# mcu.net
KiCad netlist of a schematic drawn in Altium Designer
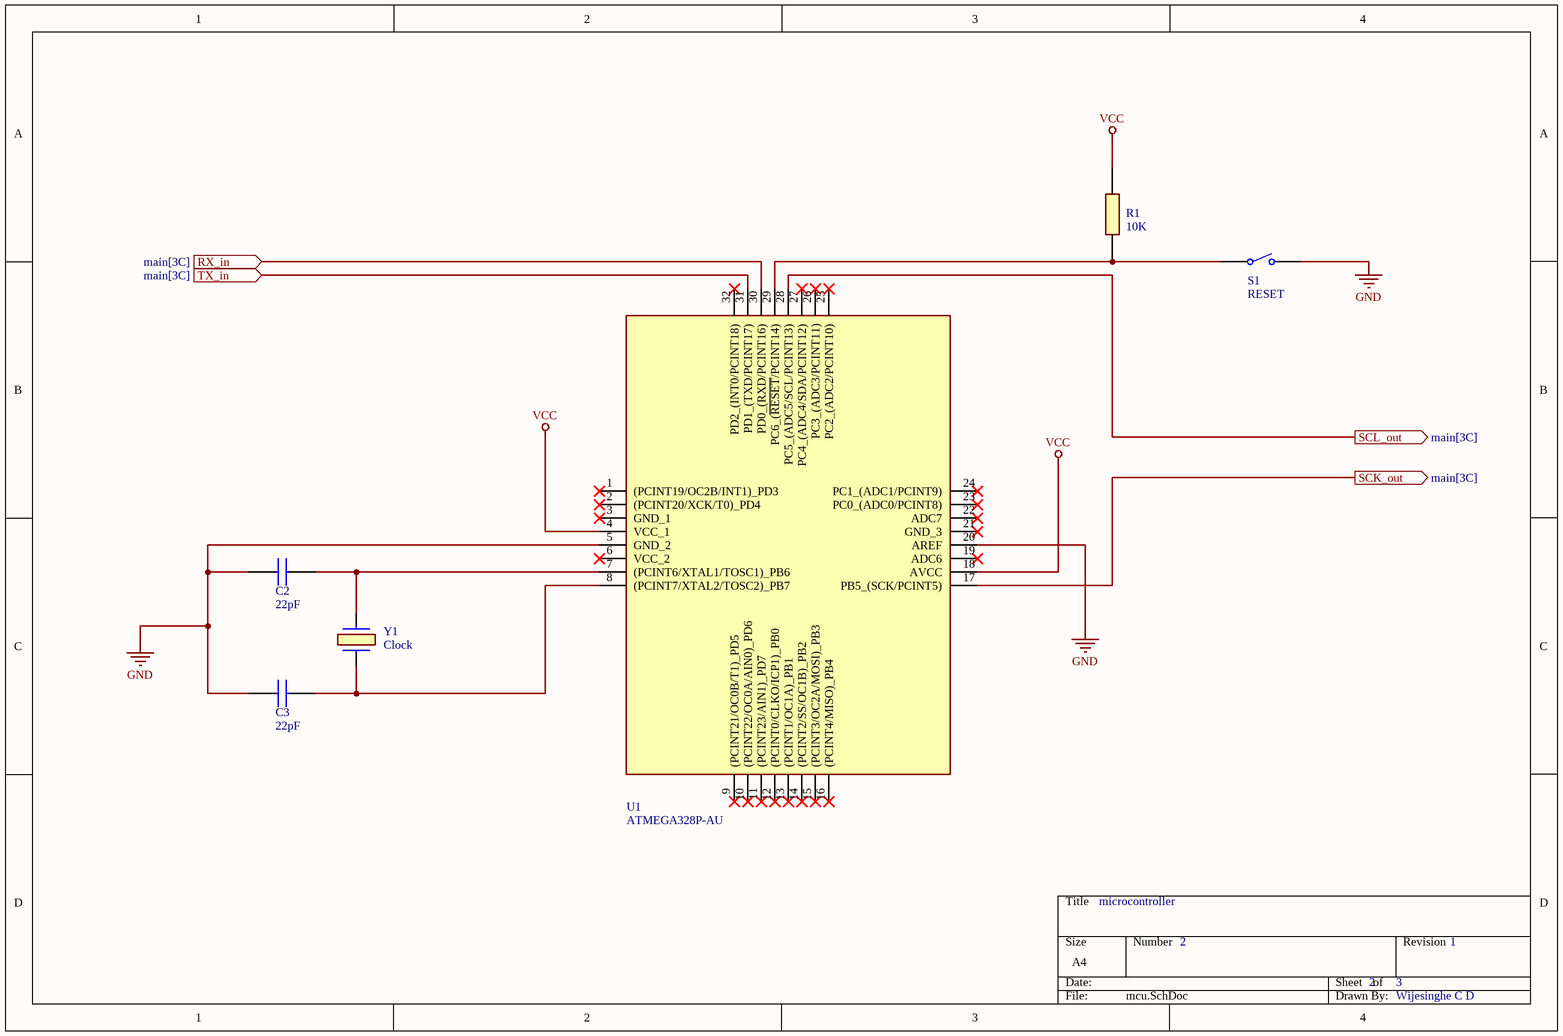
[diagram p0: mcu.SchDoc]

(export (version "E")
  (design (tool "Eeschema 10.0.6"))
  (components
    (comp (ref "C2")
      (value "22pF")
      (footprint "SamacSys:CAPC3216X100N")
      (description "Capacitor")
      (fields
        (field (name "MANUFACTURER_PART_NUMBER") "CL31C220JBCNNNC")
        (field (name "MOUSER PART NUMBER") "187-CL31C220JBCNNNC")
      )
      (libsource (lib "*") (part "CL31C220JBCNNNC"))
    )
    (comp (ref "C3")
      (value "22pF")
      (footprint "SamacSys:CAPC3216X100N")
      (description "Capacitor")
      (fields
        (field (name "MANUFACTURER_PART_NUMBER") "CL31C220JBCNNNC")
        (field (name "MOUSER PART NUMBER") "187-CL31C220JBCNNNC")
      )
      (libsource (lib "*") (part "CL31C220JBCNNNC"))
    )
    (comp (ref "R1")
      (value "10K")
      (footprint "SamacSys:RESC2012X75N")
      (description "Resistor")
      (fields
        (field (name "MANUFACTURER_PART_NUMBER") "ERJ-P6WF1002V")
        (field (name "MOUSER PART NUMBER") "667-ERJ-P6WF1002V")
      )
      (libsource (lib "*") (part "ERJ-P6WF1002V"))
    )
    (comp (ref "S1")
      (value "RESET")
      (footprint "TECO-FSMSM-2_V")
      (description "FSMSM Push Button Switch, 50 mA, -35 to 85 degC, 2-Pin SMD, RoHS, Bulk")
      (fields (field (name "MANUFACTURER") "TE Connectivity"))
      (libsource (lib "Altium Content Vault") (part "SW-SPST-2_C"))
    )
    (comp (ref "U1")
      (value "ATMEGA328P-AU")
      (footprint "SamacSys:QFP80P900X900X120-32N")
      (description "Integrated Circuit")
      (fields (field (name "MOUSER PART NUMBER") "556-ATMEGA328P-AU"))
      (libsource (lib "*") (part "ATMEGA328P-AU"))
    )
    (comp (ref "Y1")
      (value "Clock")
      (footprint "SamacSys:ECS160203XTR")
      (description "Crystal or Oscillator")
      (fields
        (field (name "MANUFACTURER_PART_NUMBER") "ECS-160-20-3X-TR")
        (field (name "MOUSER PART NUMBER") "520-160-20-3XT")
      )
      (libsource (lib "*") (part "ECS-160-20-3X-TR"))
    )
  )
  (nets
    (net (code "1") (name "/RX_in") (class "Default")
      (node (ref "U1") (pin "30") (pinfunction "PD0_(RXD/PCINT16)_30") (pintype "passive"))
    )
    (net (code "2") (name "/SCK_out") (class "Default")
      (node (ref "U1") (pin "17") (pinfunction "PB5_(SCK/PCINT5)_17") (pintype "passive"))
    )
    (net (code "3") (name "/SCL_out") (class "Default")
      (node (ref "U1") (pin "28") (pinfunction "PC5_(ADC5/SCL/PCINT13)_28") (pintype "passive"))
    )
    (net (code "4") (name "/TX_in") (class "Default")
      (node (ref "U1") (pin "31") (pinfunction "PD1_(TXD/PCINT17)_31") (pintype "passive"))
    )
    (net (code "5") (name "GND") (class "Default")
      (node (ref "C2") (pin "1") (pinfunction "1_1") (pintype "passive"))
      (node (ref "C3") (pin "1") (pinfunction "1_1") (pintype "passive"))
      (node (ref "S1") (pin "2") (pinfunction "2_2") (pintype "passive"))
      (node (ref "U1") (pin "20") (pinfunction "AREF_20") (pintype "passive"))
      (node (ref "U1") (pin "5") (pinfunction "GND_2_5") (pintype "passive"))
    )
    (net (code "6") (name "Net-(U1-(PCINT6{slash}XTAL1{slash}TOSC1)_PB6)") (class "Default")
      (node (ref "C2") (pin "2") (pinfunction "2_2") (pintype "passive"))
      (node (ref "U1") (pin "7") (pinfunction "(PCINT6/XTAL1/TOSC1)_PB6_7") (pintype "passive"))
      (node (ref "Y1") (pin "1") (pinfunction "X1_1") (pintype "passive"))
    )
    (net (code "7") (name "Net-(U1-(PCINT7{slash}XTAL2{slash}TOSC2)_PB7)") (class "Default")
      (node (ref "C3") (pin "2") (pinfunction "2_2") (pintype "passive"))
      (node (ref "U1") (pin "8") (pinfunction "(PCINT7/XTAL2/TOSC2)_PB7_8") (pintype "passive"))
      (node (ref "Y1") (pin "2") (pinfunction "X2_2") (pintype "passive"))
    )
    (net (code "8") (name "Net-(U1-PC6_(~{RESET}{slash}PCINT14))") (class "Default")
      (node (ref "R1") (pin "1") (pinfunction "1_1") (pintype "passive"))
      (node (ref "S1") (pin "1") (pinfunction "1_1") (pintype "passive"))
      (node (ref "U1") (pin "29") (pinfunction "PC6_(~{RESET}/PCINT14)_29") (pintype "passive"))
    )
    (net (code "9") (name "VCC") (class "Default")
      (node (ref "R1") (pin "2") (pinfunction "2_2") (pintype "passive"))
      (node (ref "U1") (pin "18") (pinfunction "AVCC_18") (pintype "passive"))
      (node (ref "U1") (pin "4") (pinfunction "VCC_1_4") (pintype "passive"))
    )
    (net (code "10") (name "unconnected-(U1-(PCINT0{slash}CLKO{slash}ICP1)_PB0-Pad12)") (class "Default")
      (node (ref "U1") (pin "12") (pinfunction "(PCINT0/CLKO/ICP1)_PB0_12") (pintype "passive+no_connect"))
    )
    (net (code "11") (name "unconnected-(U1-(PCINT1{slash}OC1A)_PB1-Pad13)") (class "Default")
      (node (ref "U1") (pin "13") (pinfunction "(PCINT1/OC1A)_PB1_13") (pintype "passive+no_connect"))
    )
    (net (code "12") (name "unconnected-(U1-(PCINT2{slash}SS{slash}OC1B)_PB2-Pad14)") (class "Default")
      (node (ref "U1") (pin "14") (pinfunction "(PCINT2/SS/OC1B)_PB2_14") (pintype "passive+no_connect"))
    )
    (net (code "13") (name "unconnected-(U1-(PCINT3{slash}OC2A{slash}MOSI)_PB3-Pad15)") (class "Default")
      (node (ref "U1") (pin "15") (pinfunction "(PCINT3/OC2A/MOSI)_PB3_15") (pintype "passive+no_connect"))
    )
    (net (code "14") (name "unconnected-(U1-(PCINT4{slash}MISO)_PB4-Pad16)") (class "Default")
      (node (ref "U1") (pin "16") (pinfunction "(PCINT4/MISO)_PB4_16") (pintype "passive+no_connect"))
    )
    (net (code "15") (name "unconnected-(U1-(PCINT19{slash}OC2B{slash}INT1)_PD3-Pad1)") (class "Default")
      (node (ref "U1") (pin "1") (pinfunction "(PCINT19/OC2B/INT1)_PD3_1") (pintype "passive+no_connect"))
    )
    (net (code "16") (name "unconnected-(U1-(PCINT20{slash}XCK{slash}T0)_PD4-Pad2)") (class "Default")
      (node (ref "U1") (pin "2") (pinfunction "(PCINT20/XCK/T0)_PD4_2") (pintype "passive+no_connect"))
    )
    (net (code "17") (name "unconnected-(U1-(PCINT21{slash}OC0B{slash}T1)_PD5-Pad9)") (class "Default")
      (node (ref "U1") (pin "9") (pinfunction "(PCINT21/OC0B/T1)_PD5_9") (pintype "passive+no_connect"))
    )
    (net (code "18") (name "unconnected-(U1-(PCINT22{slash}OC0A{slash}AIN0)_PD6-Pad10)") (class "Default")
      (node (ref "U1") (pin "10") (pinfunction "(PCINT22/OC0A/AIN0)_PD6_10") (pintype "passive+no_connect"))
    )
    (net (code "19") (name "unconnected-(U1-(PCINT23{slash}AIN1)_PD7-Pad11)") (class "Default")
      (node (ref "U1") (pin "11") (pinfunction "(PCINT23/AIN1)_PD7_11") (pintype "passive+no_connect"))
    )
    (net (code "20") (name "unconnected-(U1-ADC6-Pad19)") (class "Default")
      (node (ref "U1") (pin "19") (pinfunction "ADC6_19") (pintype "passive+no_connect"))
    )
    (net (code "21") (name "unconnected-(U1-ADC7-Pad22)") (class "Default")
      (node (ref "U1") (pin "22") (pinfunction "ADC7_22") (pintype "passive+no_connect"))
    )
    (net (code "22") (name "unconnected-(U1-GND_1-Pad3)") (class "Default")
      (node (ref "U1") (pin "3") (pinfunction "GND_1_3") (pintype "passive+no_connect"))
    )
    (net (code "23") (name "unconnected-(U1-GND_3-Pad21)") (class "Default")
      (node (ref "U1") (pin "21") (pinfunction "GND_3_21") (pintype "passive+no_connect"))
    )
    (net (code "24") (name "unconnected-(U1-PC0_(ADC0{slash}PCINT8)-Pad23)") (class "Default")
      (node (ref "U1") (pin "23") (pinfunction "PC0_(ADC0/PCINT8)_23") (pintype "passive+no_connect"))
    )
    (net (code "25") (name "unconnected-(U1-PC1_(ADC1{slash}PCINT9)-Pad24)") (class "Default")
      (node (ref "U1") (pin "24") (pinfunction "PC1_(ADC1/PCINT9)_24") (pintype "passive+no_connect"))
    )
    (net (code "26") (name "unconnected-(U1-PC2_(ADC2{slash}PCINT10)-Pad25)") (class "Default")
      (node (ref "U1") (pin "25") (pinfunction "PC2_(ADC2/PCINT10)_25") (pintype "passive+no_connect"))
    )
    (net (code "27") (name "unconnected-(U1-PC3_(ADC3{slash}PCINT11)-Pad26)") (class "Default")
      (node (ref "U1") (pin "26") (pinfunction "PC3_(ADC3/PCINT11)_26") (pintype "passive+no_connect"))
    )
    (net (code "28") (name "unconnected-(U1-PC4_(ADC4{slash}SDA{slash}PCINT12)-Pad27)") (class "Default")
      (node (ref "U1") (pin "27") (pinfunction "PC4_(ADC4/SDA/PCINT12)_27") (pintype "passive+no_connect"))
    )
    (net (code "29") (name "unconnected-(U1-PD2_(INT0{slash}PCINT18)-Pad32)") (class "Default")
      (node (ref "U1") (pin "32") (pinfunction "PD2_(INT0/PCINT18)_32") (pintype "passive+no_connect"))
    )
    (net (code "30") (name "unconnected-(U1-VCC_2-Pad6)") (class "Default")
      (node (ref "U1") (pin "6") (pinfunction "VCC_2_6") (pintype "passive+no_connect"))
    )
  )
)
